# badge1.net
KiCad netlist of a schematic drawn in EAGLE
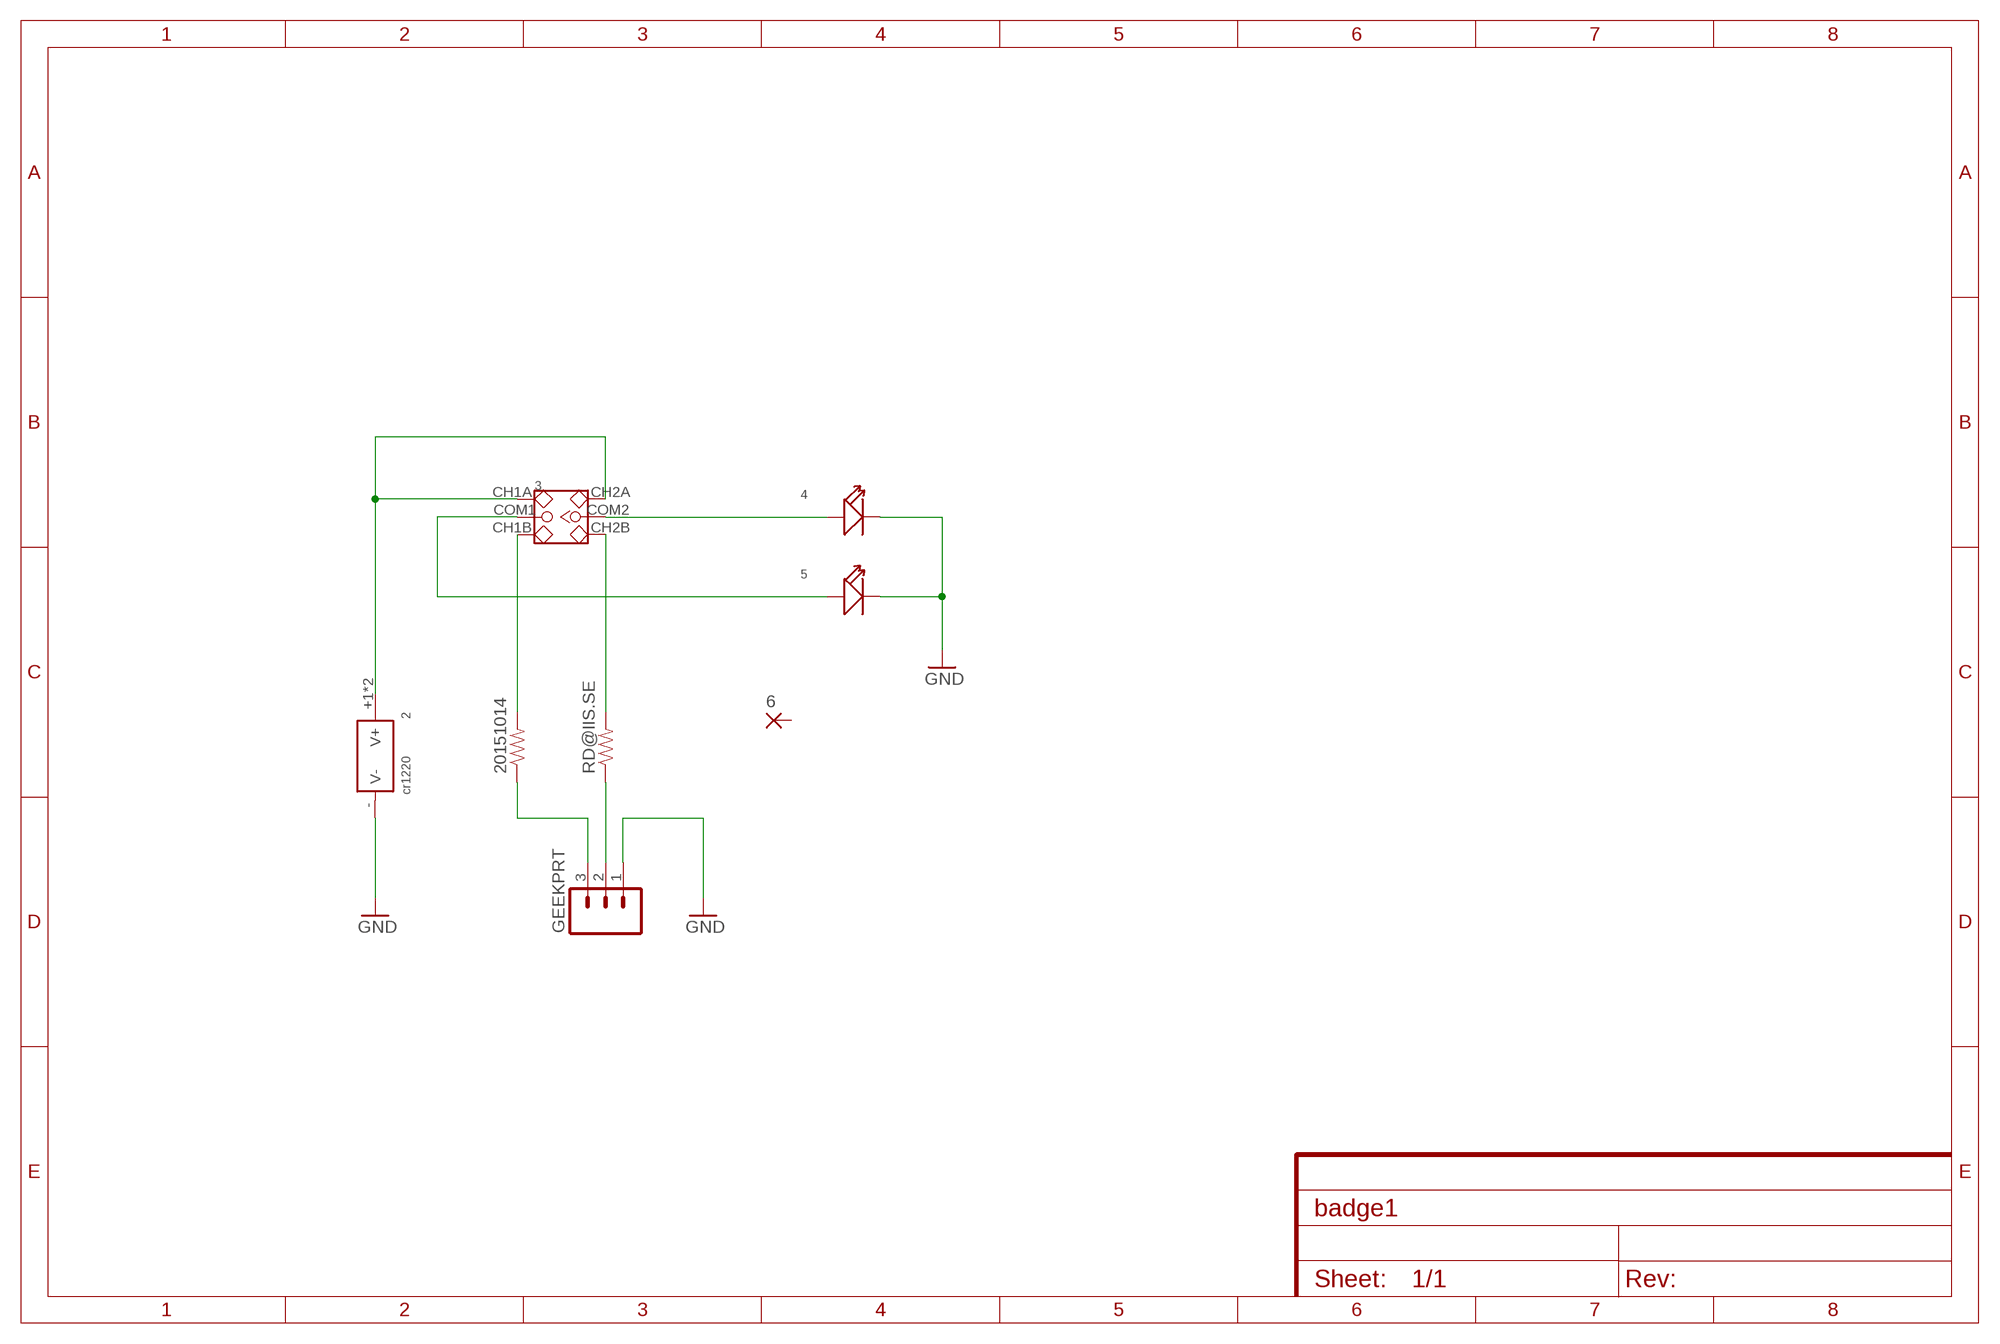
[diagram p0: schematic, sheet 1]

(export (version "E")
  (design (tool "Eeschema 10.0.6"))
  (components
    (comp (ref "2")
      (value "cr1220")
      (footprint "eagle-import:BAT2P-13.5-CR1220")
      (libsource (lib "eagle-import") (part "DIP-BATTERY-CELL-HOLDER(1220)"))
    )
    (comp (ref "3")
      (value "DIP-TOGGLE-SWITCH-2CH-(2X3P-2.54-90D)'90D'")
      (footprint "eagle-import:SW6-2.54-9.0X3.5X3.2MM-90D")
      (libsource (lib "eagle-import") (part "DIP-TOGGLE-SWITCH-2CH-(2X3P-2.54-90D)'90D'"))
    )
    (comp (ref "4")
      (value "LED'5MM'")
      (footprint "eagle-import:LED2-2.54-D5.0MM")
      (libsource (lib "eagle-import") (part "LED'5MM'"))
    )
    (comp (ref "5")
      (value "LED'5MM'")
      (footprint "eagle-import:LED2-2.54-D5.0MM")
      (libsource (lib "eagle-import") (part "LED'5MM'"))
    )
    (comp (ref "6")
      (value "3,81/1,4")
      (footprint "eagle-import:3,81_1,4")
      (libsource (lib "eagle-import") (part "3,81/1,4"))
    )
    (comp (ref "20151014")
      (value "RESISTORPTH-1/4W")
      (footprint "eagle-import:AXIAL-0.4")
      (libsource (lib "eagle-import") (part "RESISTORPTH-1/4W"))
    )
    (comp (ref "GEEKPRT")
      (value "M03LOCK")
      (footprint "eagle-import:1X03_LOCK")
      (libsource (lib "eagle-import") (part "M03LOCK"))
    )
    (comp (ref "RD@IIS.SE")
      (value "RESISTORPTH-1/4W")
      (footprint "eagle-import:AXIAL-0.4")
      (libsource (lib "eagle-import") (part "RESISTORPTH-1/4W"))
    )
  )
  (nets
    (net (code "1") (name "GND") (class "Default")
      (node (ref "2") (pin "-") (pinfunction "V-_-") (pintype "bidirectional"))
      (node (ref "4") (pin "-") (pinfunction "-_-") (pintype "passive"))
      (node (ref "5") (pin "-") (pinfunction "-_-") (pintype "passive"))
      (node (ref "GEEKPRT") (pin "1") (pinfunction "1_1") (pintype "passive"))
    )
    (net (code "2") (name "Net-(2-V+-Pad+1)") (class "Default")
      (node (ref "2") (pin "+1") (pinfunction "V+_+1") (pintype "bidirectional"))
      (node (ref "2") (pin "+2") (pinfunction "V+_+2") (pintype "bidirectional"))
      (node (ref "3") (pin "CH1A") (pinfunction "CH1A_CH1A") (pintype "bidirectional"))
      (node (ref "3") (pin "CH2A") (pinfunction "CH2A_CH2A") (pintype "bidirectional"))
    )
    (net (code "3") (name "Net-(3-PadCOM1)") (class "Default")
      (node (ref "3") (pin "COM1") (pinfunction "COM1_COM1") (pintype "bidirectional"))
      (node (ref "5") (pin "+") (pinfunction "+_+") (pintype "passive"))
    )
    (net (code "4") (name "Net-(3-PadCOM2)") (class "Default")
      (node (ref "3") (pin "COM2") (pinfunction "COM2_COM2") (pintype "bidirectional"))
      (node (ref "4") (pin "+") (pinfunction "+_+") (pintype "passive"))
    )
    (net (code "5") (name "Net-(20151014-1)") (class "Default")
      (node (ref "20151014") (pin "P$1") (pinfunction "1_P$1") (pintype "passive"))
      (node (ref "GEEKPRT") (pin "3") (pinfunction "3_3") (pintype "passive"))
    )
    (net (code "6") (name "Net-(20151014-2)") (class "Default")
      (node (ref "20151014") (pin "P$2") (pinfunction "2_P$2") (pintype "passive"))
      (node (ref "3") (pin "CH1B") (pinfunction "CH1B_CH1B") (pintype "bidirectional"))
    )
    (net (code "7") (name "Net-(RD@IIS.SE-1)") (class "Default")
      (node (ref "GEEKPRT") (pin "2") (pinfunction "2_2") (pintype "passive"))
      (node (ref "RD@IIS.SE") (pin "P$1") (pinfunction "1_P$1") (pintype "passive"))
    )
    (net (code "8") (name "Net-(RD@IIS.SE-2)") (class "Default")
      (node (ref "3") (pin "CH2B") (pinfunction "CH2B_CH2B") (pintype "bidirectional"))
      (node (ref "RD@IIS.SE") (pin "P$2") (pinfunction "2_P$2") (pintype "passive"))
    )
    (net (code "9") (name "unconnected-(6-P-Pad1)") (class "Default")
      (node (ref "6") (pin "1") (pinfunction "P_1") (pintype "passive"))
    )
  )
)
